# MCU_Power.net
KiCad netlist of a schematic drawn in Altium Designer
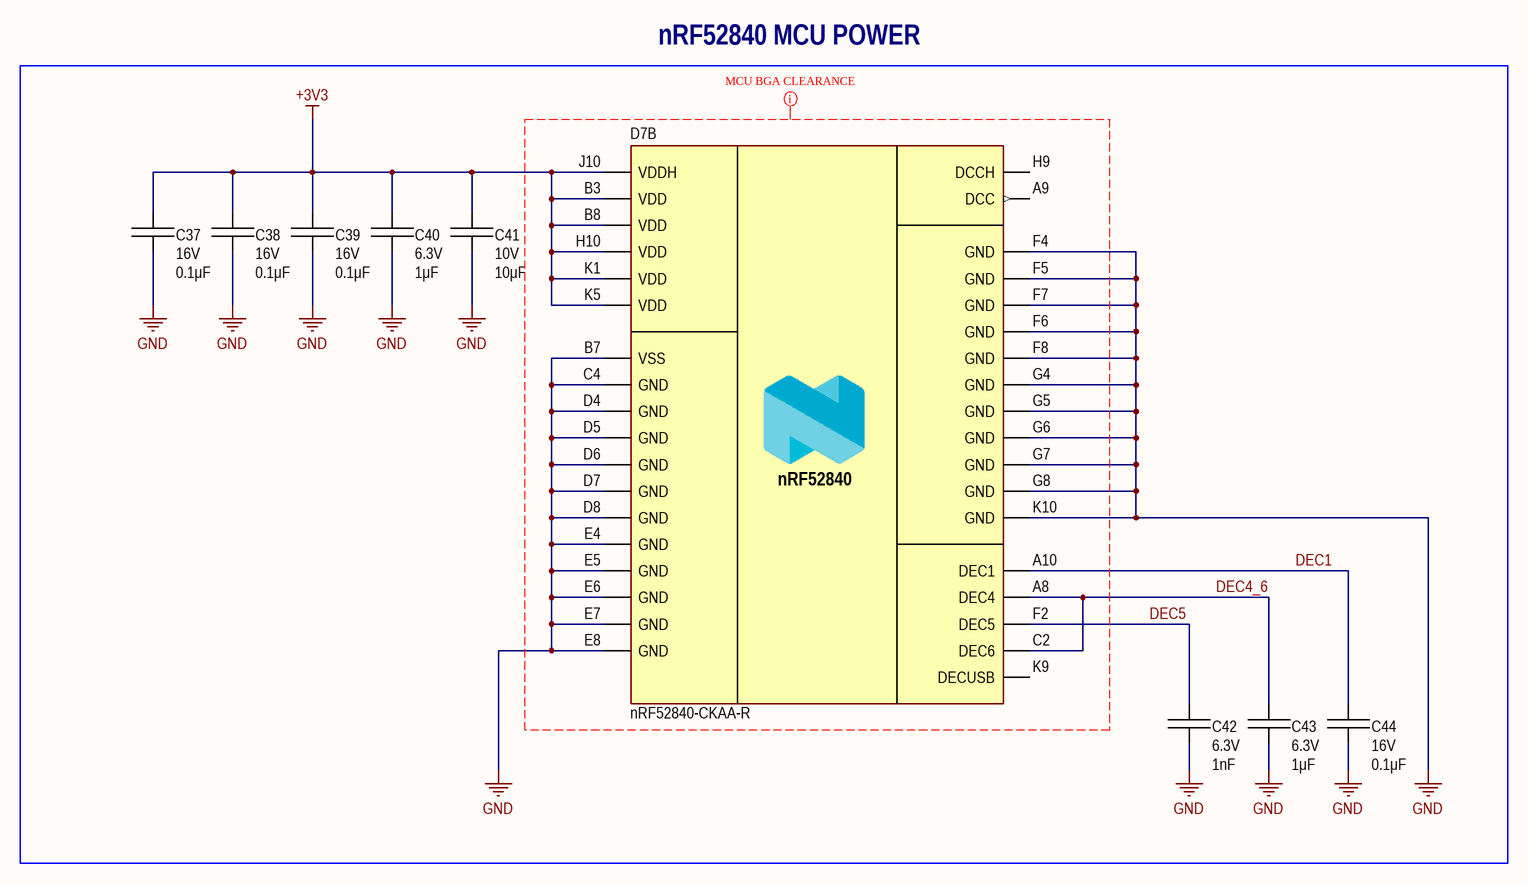
[diagram p0: MCU_Power.SchDoc]

(export (version "E")
  (design (tool "Eeschema 10.0.6"))
  (components
    (comp (ref "C37")
      (value "0.1μF")
      (footprint "CAP: 0402_NO_SILK")
      (description "0.1 µF ±10% 16V Ceramic Capacitor X7R 0402 (1005 Metric)")
      (fields
        (field (name "MANUFACTURER") "Yageo")
        (field (name "PARTNUMBER") "CC0402KRX7R7BB104")
        (field (name "VOLTAGE") "16V")
      )
      (libsource (lib "capacitor") (part "Ceramic_0402"))
    )
    (comp (ref "C38")
      (value "0.1μF")
      (footprint "CAP: 0402_NO_SILK")
      (description "0.1 µF ±10% 16V Ceramic Capacitor X7R 0402 (1005 Metric)")
      (fields
        (field (name "MANUFACTURER") "Yageo")
        (field (name "PARTNUMBER") "CC0402KRX7R7BB104")
        (field (name "VOLTAGE") "16V")
      )
      (libsource (lib "capacitor") (part "Ceramic_0402"))
    )
    (comp (ref "C39")
      (value "0.1μF")
      (footprint "CAP: 0402_NO_SILK")
      (description "0.1 µF ±10% 16V Ceramic Capacitor X7R 0402 (1005 Metric)")
      (fields
        (field (name "MANUFACTURER") "Yageo")
        (field (name "PARTNUMBER") "CC0402KRX7R7BB104")
        (field (name "VOLTAGE") "16V")
      )
      (libsource (lib "capacitor") (part "Ceramic_0402"))
    )
    (comp (ref "C40")
      (value "1μF")
      (footprint "CAP: 0402_NO_SILK")
      (description "0.1 µF ±10% 16V Ceramic Capacitor X7R 0402 (1005 Metric)")
      (fields
        (field (name "MANUFACTURER") "Yageo")
        (field (name "PARTNUMBER") "CC0402KRX7R5BB105")
        (field (name "VOLTAGE") "6.3V")
      )
      (libsource (lib "capacitor") (part "Ceramic_0402"))
    )
    (comp (ref "C41")
      (value "10μF")
      (footprint "CAP: 0805")
      (description "10 µF ±10% 10V Ceramic Capacitor X7R 0805 (2012 Metric)")
      (fields
        (field (name "MANUFACTURER") "Yageo")
        (field (name "PARTNUMBER") "CC0805KFX7R6BB106")
        (field (name "VOLTAGE") "10V")
      )
      (libsource (lib "capacitor") (part "Ceramic_0805"))
    )
    (comp (ref "C42")
      (value "1nF")
      (footprint "CAP: 0402_NO_SILK")
      (description "1000 pF ±5% 25V Ceramic Capacitor C0G, NP0 0402 (1005 Metric)")
      (fields
        (field (name "MANUFACTURER") "Yageo")
        (field (name "PARTNUMBER") "CC0402JRNPO8BN102")
        (field (name "VOLTAGE") "6.3V")
      )
      (libsource (lib "capacitor") (part "Ceramic_0402"))
    )
    (comp (ref "C43")
      (value "1μF")
      (footprint "CAP: 0402_NO_SILK")
      (description "0.1 µF ±10% 16V Ceramic Capacitor X7R 0402 (1005 Metric)")
      (fields
        (field (name "MANUFACTURER") "Yageo")
        (field (name "PARTNUMBER") "CC0402KRX7R5BB105")
        (field (name "VOLTAGE") "6.3V")
      )
      (libsource (lib "capacitor") (part "Ceramic_0402"))
    )
    (comp (ref "C44")
      (value "0.1μF")
      (footprint "CAP: 0402_NO_SILK")
      (description "0.1 µF ±10% 16V Ceramic Capacitor X7R 0402 (1005 Metric)")
      (fields
        (field (name "MANUFACTURER") "Yageo")
        (field (name "PARTNUMBER") "CC0402KRX7R7BB104")
        (field (name "VOLTAGE") "16V")
      )
      (libsource (lib "capacitor") (part "Ceramic_0402"))
    )
    (comp (ref "D7")
      (value "~")
      (footprint "MCU: nRF52840_WLCP93")
      (description "MCU")
      (fields
        (field (name "MANUFACTURER") "Nordic Semiconductor")
        (field (name "VALUEMANUFACTURERPARTNUMBER") "IC microcontroller, 32bit, Cortex-M4, 64 MHz, 1 MB, 256 kB, , , 93-WLCSP")
        (field (name "PARTNUMBER") "nRF52840-CKAA-R")
      )
      (libsource (lib "MyLib") (part "nRF52840"))
    )
  )
  (nets
    (net (code "1") (name "+3V3") (class "Default")
      (node (ref "C37") (pin "2") (pinfunction "2_2") (pintype "passive"))
      (node (ref "C38") (pin "2") (pinfunction "2_2") (pintype "passive"))
      (node (ref "C39") (pin "2") (pinfunction "2_2") (pintype "passive"))
      (node (ref "C40") (pin "2") (pinfunction "2_2") (pintype "passive"))
      (node (ref "C41") (pin "2") (pinfunction "2_2") (pintype "passive"))
      (node (ref "D7") (pin "B3") (pinfunction "VDD_B3") (pintype "power_in"))
      (node (ref "D7") (pin "B8") (pinfunction "VDD_B8") (pintype "power_in"))
      (node (ref "D7") (pin "H10") (pinfunction "VDD_H10") (pintype "power_in"))
      (node (ref "D7") (pin "J10") (pinfunction "VDDH_J10") (pintype "power_in"))
      (node (ref "D7") (pin "K1") (pinfunction "VDD_K1") (pintype "power_in"))
      (node (ref "D7") (pin "K5") (pinfunction "VDD_K5") (pintype "power_in"))
    )
    (net (code "2") (name "/DEC1") (class "Default")
      (node (ref "C44") (pin "2") (pinfunction "2_2") (pintype "passive"))
      (node (ref "D7") (pin "A10") (pinfunction "DEC1_A10") (pintype "power_in"))
    )
    (net (code "3") (name "/DEC4_6") (class "Default")
      (node (ref "C43") (pin "2") (pinfunction "2_2") (pintype "passive"))
      (node (ref "D7") (pin "A8") (pinfunction "DEC4_A8") (pintype "power_in"))
      (node (ref "D7") (pin "C2") (pinfunction "DEC6_C2") (pintype "power_in"))
    )
    (net (code "4") (name "/DEC5") (class "Default")
      (node (ref "C42") (pin "2") (pinfunction "2_2") (pintype "passive"))
      (node (ref "D7") (pin "F2") (pinfunction "DEC5_F2") (pintype "power_in"))
    )
    (net (code "5") (name "GND") (class "Default")
      (node (ref "C37") (pin "1") (pinfunction "1_1") (pintype "passive"))
      (node (ref "C38") (pin "1") (pinfunction "1_1") (pintype "passive"))
      (node (ref "C39") (pin "1") (pinfunction "1_1") (pintype "passive"))
      (node (ref "C40") (pin "1") (pinfunction "1_1") (pintype "passive"))
      (node (ref "C41") (pin "1") (pinfunction "1_1") (pintype "passive"))
      (node (ref "C42") (pin "1") (pinfunction "1_1") (pintype "passive"))
      (node (ref "C43") (pin "1") (pinfunction "1_1") (pintype "passive"))
      (node (ref "C44") (pin "1") (pinfunction "1_1") (pintype "passive"))
      (node (ref "D7") (pin "B7") (pinfunction "VSS_B7") (pintype "power_in"))
      (node (ref "D7") (pin "C4") (pinfunction "GND_C4") (pintype "power_in"))
      (node (ref "D7") (pin "D4") (pinfunction "GND_D4") (pintype "power_in"))
      (node (ref "D7") (pin "D5") (pinfunction "GND_D5") (pintype "power_in"))
      (node (ref "D7") (pin "D6") (pinfunction "GND_D6") (pintype "power_in"))
      (node (ref "D7") (pin "D7") (pinfunction "GND_D7") (pintype "power_in"))
      (node (ref "D7") (pin "D8") (pinfunction "GND_D8") (pintype "power_in"))
      (node (ref "D7") (pin "E4") (pinfunction "GND_E4") (pintype "power_in"))
      (node (ref "D7") (pin "E5") (pinfunction "GND_E5") (pintype "power_in"))
      (node (ref "D7") (pin "E6") (pinfunction "GND_E6") (pintype "power_in"))
      (node (ref "D7") (pin "E7") (pinfunction "GND_E7") (pintype "power_in"))
      (node (ref "D7") (pin "E8") (pinfunction "GND_E8") (pintype "power_in"))
      (node (ref "D7") (pin "F4") (pinfunction "GND_F4") (pintype "power_in"))
      (node (ref "D7") (pin "F5") (pinfunction "GND_F5") (pintype "power_in"))
      (node (ref "D7") (pin "F6") (pinfunction "GND_F6") (pintype "power_in"))
      (node (ref "D7") (pin "F7") (pinfunction "GND_F7") (pintype "power_in"))
      (node (ref "D7") (pin "F8") (pinfunction "GND_F8") (pintype "power_in"))
      (node (ref "D7") (pin "G4") (pinfunction "GND_G4") (pintype "power_in"))
      (node (ref "D7") (pin "G5") (pinfunction "GND_G5") (pintype "power_in"))
      (node (ref "D7") (pin "G6") (pinfunction "GND_G6") (pintype "power_in"))
      (node (ref "D7") (pin "G7") (pinfunction "GND_G7") (pintype "power_in"))
      (node (ref "D7") (pin "G8") (pinfunction "GND_G8") (pintype "power_in"))
      (node (ref "D7") (pin "K10") (pinfunction "GND_K10") (pintype "power_in"))
    )
    (net (code "6") (name "unconnected-(D7B-DCC-PadA9)") (class "Default")
      (node (ref "D7") (pin "A9") (pinfunction "DCC_A9") (pintype "output"))
    )
    (net (code "7") (name "unconnected-(D7B-DCCH-PadH9)") (class "Default")
      (node (ref "D7") (pin "H9") (pinfunction "DCCH_H9") (pintype "power_in"))
    )
    (net (code "8") (name "unconnected-(D7B-DECUSB-PadK9)") (class "Default")
      (node (ref "D7") (pin "K9") (pinfunction "DECUSB_K9") (pintype "power_in"))
    )
  )
)
